# Rs232Iso-due.net
KiCad netlist of a schematic drawn in EAGLE
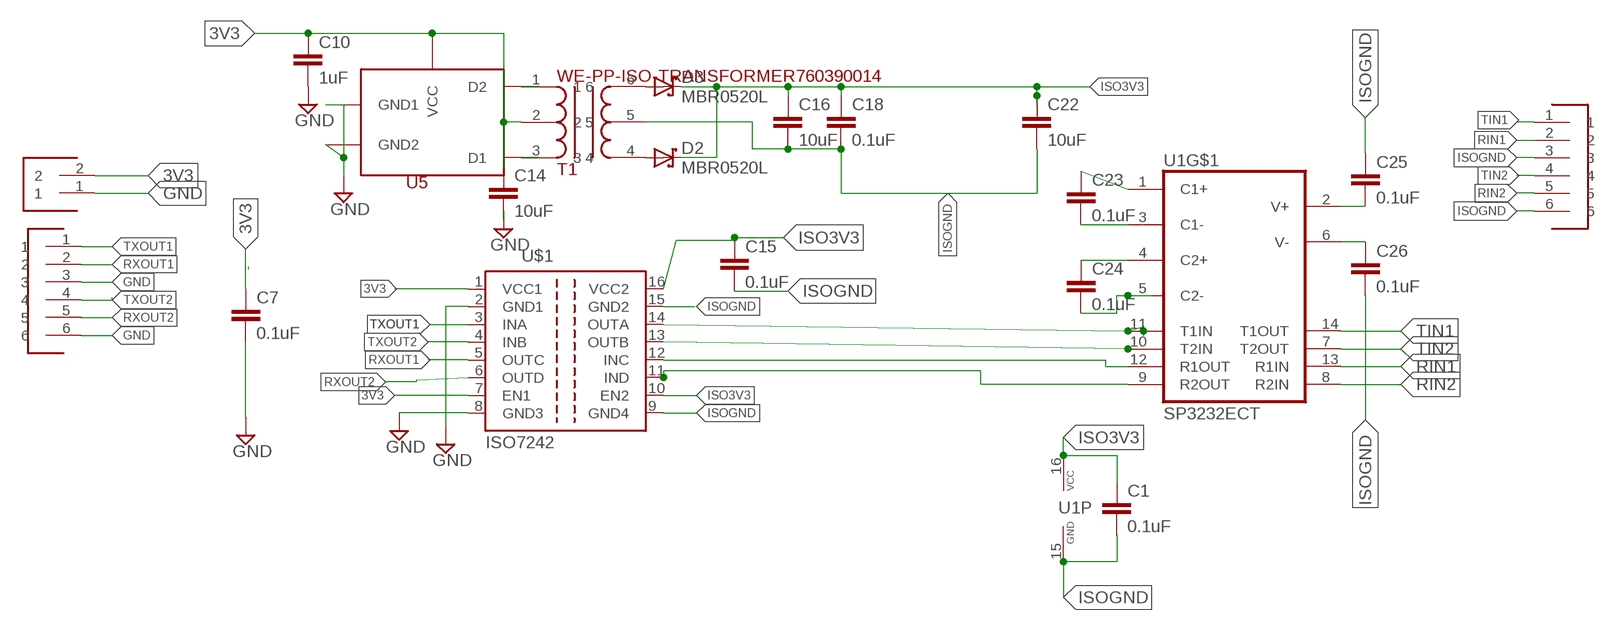
[diagram p0: schematic, sheet 1]

(export (version "E")
  (design (tool "Eeschema 10.0.6"))
  (components
    (comp (ref "C1")
      (value "0.1uF")
      (footprint "eagle-import:0603")
      (libsource (lib "eagle-import") (part "CAP0603"))
    )
    (comp (ref "C7")
      (value "0.1uF")
      (footprint "eagle-import:0603")
      (libsource (lib "eagle-import") (part "CAP0603"))
    )
    (comp (ref "C10")
      (value "1uF")
      (footprint "eagle-import:0805")
      (libsource (lib "eagle-import") (part "CAP0805"))
    )
    (comp (ref "C14")
      (value "10uF")
      (footprint "eagle-import:0805")
      (libsource (lib "eagle-import") (part "CAP0805"))
    )
    (comp (ref "C15")
      (value "0.1uF")
      (footprint "eagle-import:0603")
      (libsource (lib "eagle-import") (part "CAP0603"))
    )
    (comp (ref "C16")
      (value "10uF")
      (footprint "eagle-import:0805")
      (libsource (lib "eagle-import") (part "CAP0805"))
    )
    (comp (ref "C18")
      (value "0.1uF")
      (footprint "eagle-import:0805")
      (libsource (lib "eagle-import") (part "CAP0805"))
    )
    (comp (ref "C22")
      (value "10uF")
      (footprint "eagle-import:0805")
      (libsource (lib "eagle-import") (part "CAP0805"))
    )
    (comp (ref "C23")
      (value "0.1uF")
      (footprint "eagle-import:0603")
      (libsource (lib "eagle-import") (part "CAP0603"))
    )
    (comp (ref "C24")
      (value "0.1uF")
      (footprint "eagle-import:0603")
      (libsource (lib "eagle-import") (part "CAP0603"))
    )
    (comp (ref "C25")
      (value "0.1uF")
      (footprint "eagle-import:0603")
      (libsource (lib "eagle-import") (part "CAP0603"))
    )
    (comp (ref "C26")
      (value "0.1uF")
      (footprint "eagle-import:0603")
      (libsource (lib "eagle-import") (part "CAP0603"))
    )
    (comp (ref "D2")
      (value "MBR0520L")
      (footprint "eagle-import:SOD123")
      (libsource (lib "eagle-import") (part "MBR0520L"))
    )
    (comp (ref "D3")
      (value "MBR0520L")
      (footprint "eagle-import:SOD123")
      (libsource (lib "eagle-import") (part "MBR0520L"))
    )
    (comp (ref "J1")
      (value "CON-2STD-2.54")
      (footprint "eagle-import:CON-2")
      (libsource (lib "eagle-import") (part "CON-2STD-2.54"))
    )
    (comp (ref "J2")
      (value "CON-6")
      (footprint "eagle-import:CON-6")
      (libsource (lib "eagle-import") (part "CON-6"))
    )
    (comp (ref "J4")
      (value "CON-6")
      (footprint "eagle-import:CON-6")
      (libsource (lib "eagle-import") (part "CON-6"))
    )
    (comp (ref "T1")
      (value "WE-PP-ISO-TRANSFORMER760390014")
      (footprint "eagle-import:WE_TRANSFORMER")
      (libsource (lib "eagle-import") (part "WE-PP-ISO-TRANSFORMER760390014"))
    )
    (comp (ref "U$1")
      (value "ISO7242")
      (footprint "eagle-import:SO-G16")
      (libsource (lib "eagle-import") (part "ISO7242"))
    )
    (comp (ref "U1")
      (value "SP3232ECT")
      (footprint "eagle-import:SO16")
      (libsource (lib "eagle-import") (part "SP3232ECT"))
    )
    (comp (ref "U5")
      (value "SN6501DBVT")
      (footprint "eagle-import:SOT23-5L")
      (libsource (lib "eagle-import") (part "SN6501DBVT"))
    )
  )
  (nets
    (net (code "1") (name "3V3") (class "Default")
      (node (ref "C10") (pin "1") (pinfunction "1_1") (pintype "passive"))
      (node (ref "C14") (pin "1") (pinfunction "1_1") (pintype "passive"))
      (node (ref "C7") (pin "1") (pinfunction "1_1") (pintype "passive"))
      (node (ref "J1") (pin "2") (pinfunction "2_2") (pintype "bidirectional"))
      (node (ref "T1") (pin "2") (pinfunction "2_2") (pintype "input"))
      (node (ref "U$1") (pin "1") (pinfunction "VCC1_1") (pintype "power_in"))
      (node (ref "U$1") (pin "7") (pinfunction "EN1_7") (pintype "bidirectional"))
      (node (ref "U5") (pin "2") (pinfunction "VCC_2") (pintype "bidirectional"))
    )
    (net (code "2") (name "GND") (class "Default")
      (node (ref "C10") (pin "2") (pinfunction "2_2") (pintype "passive"))
      (node (ref "C14") (pin "2") (pinfunction "2_2") (pintype "passive"))
      (node (ref "C7") (pin "2") (pinfunction "2_2") (pintype "passive"))
      (node (ref "J1") (pin "1") (pinfunction "1_1") (pintype "bidirectional"))
      (node (ref "J4") (pin "3") (pinfunction "3_3") (pintype "bidirectional"))
      (node (ref "J4") (pin "6") (pinfunction "6_6") (pintype "bidirectional"))
      (node (ref "U$1") (pin "2") (pinfunction "GND1_2") (pintype "power_in"))
      (node (ref "U$1") (pin "8") (pinfunction "GND3_8") (pintype "power_in"))
      (node (ref "U5") (pin "4") (pinfunction "GND1_4") (pintype "bidirectional"))
      (node (ref "U5") (pin "5") (pinfunction "GND2_5") (pintype "bidirectional"))
    )
    (net (code "3") (name "ISO3V3") (class "Default")
      (node (ref "C1") (pin "1") (pinfunction "1_1") (pintype "passive"))
      (node (ref "C15") (pin "1") (pinfunction "1_1") (pintype "passive"))
      (node (ref "C16") (pin "1") (pinfunction "1_1") (pintype "passive"))
      (node (ref "C18") (pin "1") (pinfunction "1_1") (pintype "passive"))
      (node (ref "C22") (pin "1") (pinfunction "1_1") (pintype "passive"))
      (node (ref "D2") (pin "C") (pinfunction "C_C") (pintype "passive"))
      (node (ref "D3") (pin "C") (pinfunction "C_C") (pintype "passive"))
      (node (ref "U$1") (pin "10") (pinfunction "EN2_10") (pintype "bidirectional"))
      (node (ref "U$1") (pin "16") (pinfunction "VCC2_16") (pintype "power_in"))
      (node (ref "U1") (pin "16") (pinfunction "VCC_16") (pintype "power_in"))
    )
    (net (code "4") (name "ISOGND") (class "Default")
      (node (ref "C1") (pin "2") (pinfunction "2_2") (pintype "passive"))
      (node (ref "C15") (pin "2") (pinfunction "2_2") (pintype "passive"))
      (node (ref "C16") (pin "2") (pinfunction "2_2") (pintype "passive"))
      (node (ref "C18") (pin "2") (pinfunction "2_2") (pintype "passive"))
      (node (ref "C22") (pin "2") (pinfunction "2_2") (pintype "passive"))
      (node (ref "C25") (pin "1") (pinfunction "1_1") (pintype "passive"))
      (node (ref "C26") (pin "2") (pinfunction "2_2") (pintype "passive"))
      (node (ref "J2") (pin "3") (pinfunction "3_3") (pintype "bidirectional"))
      (node (ref "J2") (pin "6") (pinfunction "6_6") (pintype "bidirectional"))
      (node (ref "T1") (pin "5") (pinfunction "5_5") (pintype "passive"))
      (node (ref "U$1") (pin "15") (pinfunction "GND2_15") (pintype "power_in"))
      (node (ref "U$1") (pin "9") (pinfunction "GND4_9") (pintype "bidirectional"))
      (node (ref "U1") (pin "15") (pinfunction "GND_15") (pintype "power_in"))
    )
    (net (code "5") (name "Net-(D2-PadA)") (class "Default")
      (node (ref "D2") (pin "A") (pinfunction "A_A") (pintype "passive"))
      (node (ref "T1") (pin "4") (pinfunction "4_4") (pintype "passive"))
    )
    (net (code "6") (name "Net-(D3-PadA)") (class "Default")
      (node (ref "D3") (pin "A") (pinfunction "A_A") (pintype "passive"))
      (node (ref "T1") (pin "6") (pinfunction "6_6") (pintype "passive"))
    )
    (net (code "7") (name "Net-(U$1-INC)") (class "Default")
      (node (ref "U$1") (pin "12") (pinfunction "INC_12") (pintype "bidirectional"))
      (node (ref "U1") (pin "12") (pinfunction "R1OUT_12") (pintype "output"))
    )
    (net (code "8") (name "Net-(U$1-IND)") (class "Default")
      (node (ref "U$1") (pin "11") (pinfunction "IND_11") (pintype "bidirectional"))
      (node (ref "U1") (pin "9") (pinfunction "R2OUT_9") (pintype "output"))
    )
    (net (code "9") (name "Net-(U$1-OUTA)") (class "Default")
      (node (ref "U$1") (pin "14") (pinfunction "OUTA_14") (pintype "output"))
      (node (ref "U1") (pin "11") (pinfunction "T1IN_11") (pintype "input"))
    )
    (net (code "10") (name "Net-(U$1-OUTB)") (class "Default")
      (node (ref "U$1") (pin "13") (pinfunction "OUTB_13") (pintype "output"))
      (node (ref "U1") (pin "10") (pinfunction "T2IN_10") (pintype "input"))
    )
    (net (code "11") (name "Net-(U1A-C1+)") (class "Default")
      (node (ref "C23") (pin "1") (pinfunction "1_1") (pintype "passive"))
      (node (ref "U1") (pin "1") (pinfunction "C1+_1") (pintype "bidirectional"))
    )
    (net (code "12") (name "Net-(U1A-C1-)") (class "Default")
      (node (ref "C23") (pin "2") (pinfunction "2_2") (pintype "passive"))
      (node (ref "U1") (pin "3") (pinfunction "C1-_3") (pintype "bidirectional"))
    )
    (net (code "13") (name "Net-(U1A-C2+)") (class "Default")
      (node (ref "C24") (pin "1") (pinfunction "1_1") (pintype "passive"))
      (node (ref "U1") (pin "4") (pinfunction "C2+_4") (pintype "bidirectional"))
    )
    (net (code "14") (name "Net-(U1A-C2-)") (class "Default")
      (node (ref "C24") (pin "2") (pinfunction "2_2") (pintype "passive"))
      (node (ref "U1") (pin "5") (pinfunction "C2-_5") (pintype "bidirectional"))
    )
    (net (code "15") (name "Net-(U1A-V+)") (class "Default")
      (node (ref "C25") (pin "2") (pinfunction "2_2") (pintype "passive"))
      (node (ref "U1") (pin "2") (pinfunction "V+_2") (pintype "bidirectional"))
    )
    (net (code "16") (name "Net-(U1A-V-)") (class "Default")
      (node (ref "C26") (pin "1") (pinfunction "1_1") (pintype "passive"))
      (node (ref "U1") (pin "6") (pinfunction "V-_6") (pintype "bidirectional"))
    )
    (net (code "17") (name "Net-(U5-D1)") (class "Default")
      (node (ref "T1") (pin "3") (pinfunction "3_3") (pintype "input"))
      (node (ref "U5") (pin "1") (pinfunction "D1_1") (pintype "bidirectional"))
    )
    (net (code "18") (name "Net-(U5-D2)") (class "Default")
      (node (ref "T1") (pin "1") (pinfunction "1_1") (pintype "input"))
      (node (ref "U5") (pin "3") (pinfunction "D2_3") (pintype "bidirectional"))
    )
    (net (code "19") (name "RIN1") (class "Default")
      (node (ref "J2") (pin "2") (pinfunction "2_2") (pintype "bidirectional"))
      (node (ref "U1") (pin "13") (pinfunction "R1IN_13") (pintype "input"))
    )
    (net (code "20") (name "RIN2") (class "Default")
      (node (ref "J2") (pin "5") (pinfunction "5_5") (pintype "bidirectional"))
      (node (ref "U1") (pin "8") (pinfunction "R2IN_8") (pintype "input"))
    )
    (net (code "21") (name "RXOUT1") (class "Default")
      (node (ref "J4") (pin "2") (pinfunction "2_2") (pintype "bidirectional"))
      (node (ref "U$1") (pin "5") (pinfunction "OUTC_5") (pintype "bidirectional"))
    )
    (net (code "22") (name "RXOUT2") (class "Default")
      (node (ref "J4") (pin "5") (pinfunction "5_5") (pintype "bidirectional"))
      (node (ref "U$1") (pin "6") (pinfunction "OUTD_6") (pintype "bidirectional"))
    )
    (net (code "23") (name "TIN1") (class "Default")
      (node (ref "J2") (pin "1") (pinfunction "1_1") (pintype "bidirectional"))
      (node (ref "U1") (pin "14") (pinfunction "T1OUT_14") (pintype "output"))
    )
    (net (code "24") (name "TIN2") (class "Default")
      (node (ref "J2") (pin "4") (pinfunction "4_4") (pintype "bidirectional"))
      (node (ref "U1") (pin "7") (pinfunction "T2OUT_7") (pintype "output"))
    )
    (net (code "25") (name "TXOUT1") (class "Default")
      (node (ref "J4") (pin "1") (pinfunction "1_1") (pintype "bidirectional"))
      (node (ref "U$1") (pin "3") (pinfunction "INA_3") (pintype "input"))
    )
    (net (code "26") (name "TXOUT2") (class "Default")
      (node (ref "J4") (pin "4") (pinfunction "4_4") (pintype "bidirectional"))
      (node (ref "U$1") (pin "4") (pinfunction "INB_4") (pintype "input"))
    )
  )
)
